# Qwiic_EEPROM.net
KiCad netlist of a schematic drawn in EAGLE
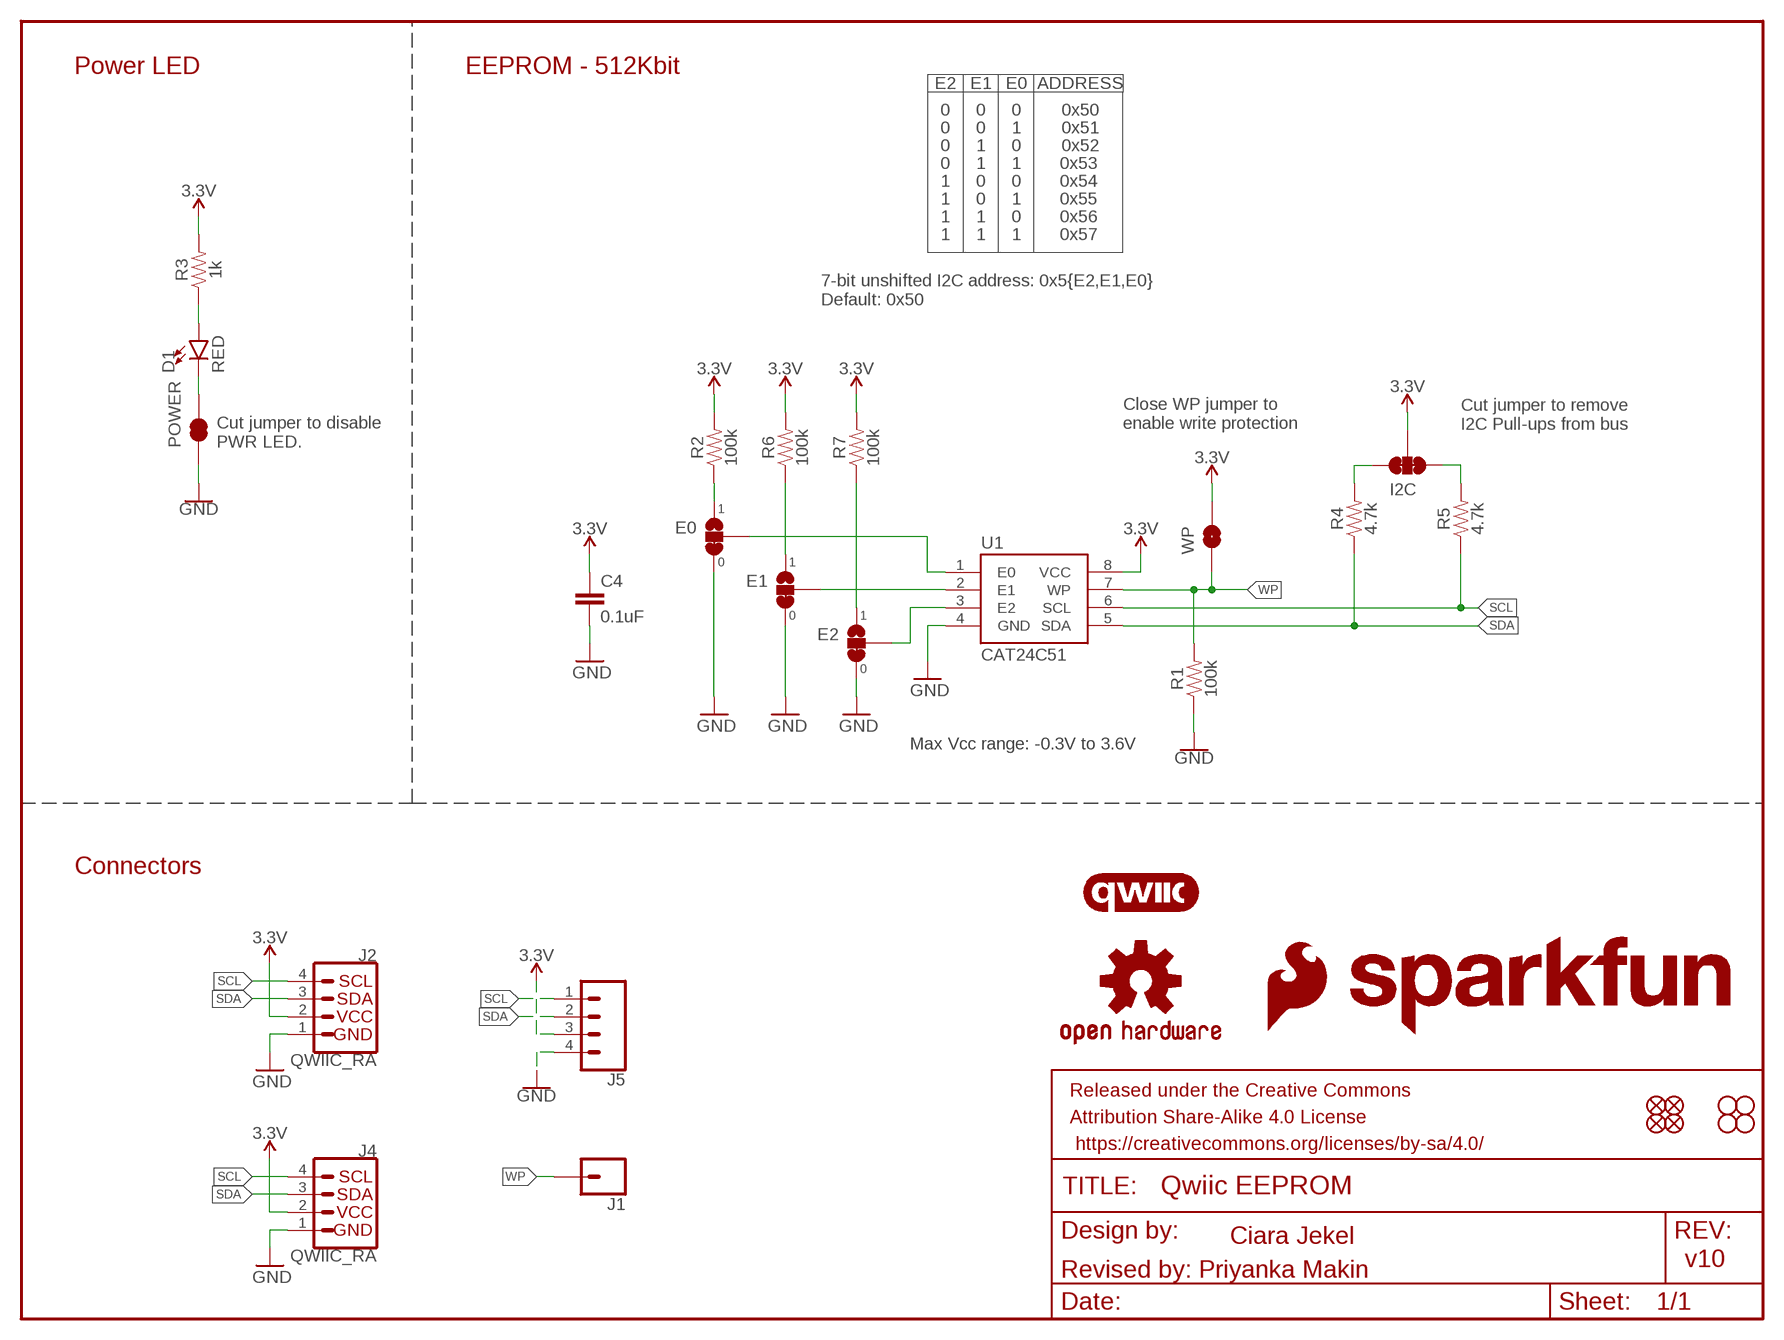
[diagram p0: schematic, sheet 1]

(export (version "E")
  (design (tool "Eeschema 10.0.6"))
  (components
    (comp (ref "C4")
      (value "0.1uF")
      (footprint "eagle-import:0603")
      (libsource (lib "eagle-import") (part "0.1UF-0603-25V-(+80/-20%)"))
    )
    (comp (ref "D1")
      (value "RED")
      (footprint "eagle-import:LED-0603")
      (libsource (lib "eagle-import") (part "LED-RED0603"))
    )
    (comp (ref "E0")
      (value "JUMPER-SMT_3_1-NC_TRACE_SILK")
      (footprint "eagle-import:SMT-JUMPER_3_1-NC_TRACE_SILK")
      (libsource (lib "eagle-import") (part "JUMPER-SMT_3_1-NC_TRACE_SILK"))
    )
    (comp (ref "E1")
      (value "JUMPER-SMT_3_1-NC_TRACE_SILK")
      (footprint "eagle-import:SMT-JUMPER_3_1-NC_TRACE_SILK")
      (libsource (lib "eagle-import") (part "JUMPER-SMT_3_1-NC_TRACE_SILK"))
    )
    (comp (ref "E2")
      (value "JUMPER-SMT_3_1-NC_TRACE_SILK")
      (footprint "eagle-import:SMT-JUMPER_3_1-NC_TRACE_SILK")
      (libsource (lib "eagle-import") (part "JUMPER-SMT_3_1-NC_TRACE_SILK"))
    )
    (comp (ref "FRAME1")
      (value "FRAME-LETTER")
      (footprint "eagle-import:CREATIVE_COMMONS")
      (libsource (lib "eagle-import") (part "FRAME-LETTER"))
    )
    (comp (ref "I2C")
      (value "JUMPER-SMT_3_2-NC_TRACE_SILK")
      (footprint "eagle-import:SMT-JUMPER_3_2-NC_TRACE_SILK")
      (libsource (lib "eagle-import") (part "JUMPER-SMT_3_2-NC_TRACE_SILK"))
    )
    (comp (ref "J1")
      (value "CONN_01PTH_NO_SILK_YES_STOP")
      (footprint "eagle-import:1X01_NO_SILK")
      (libsource (lib "eagle-import") (part "CONN_01PTH_NO_SILK_YES_STOP"))
    )
    (comp (ref "J2")
      (value "QWIIC_RA")
      (footprint "eagle-import:JST04_1MM_RA")
      (libsource (lib "eagle-import") (part "QWIIC_CONNECTORJS-1MM"))
    )
    (comp (ref "J4")
      (value "QWIIC_RA")
      (footprint "eagle-import:JST04_1MM_RA")
      (libsource (lib "eagle-import") (part "QWIIC_CONNECTORJS-1MM"))
    )
    (comp (ref "J5")
      (value "CONN_041X04_NO_SILK_NO_POP")
      (footprint "eagle-import:1X04_NO_SILK")
      (libsource (lib "eagle-import") (part "CONN_041X04_NO_SILK_NO_POP"))
    )
    (comp (ref "JP1")
      (value "FIDUCIALUFIDUCIAL")
      (footprint "eagle-import:FIDUCIAL-MICRO")
      (libsource (lib "eagle-import") (part "FIDUCIALUFIDUCIAL"))
    )
    (comp (ref "JP2")
      (value "FIDUCIALUFIDUCIAL")
      (footprint "eagle-import:FIDUCIAL-MICRO")
      (libsource (lib "eagle-import") (part "FIDUCIALUFIDUCIAL"))
    )
    (comp (ref "JP3")
      (value "STAND-OFF")
      (footprint "eagle-import:STAND-OFF")
      (libsource (lib "eagle-import") (part "STAND-OFF"))
    )
    (comp (ref "JP4")
      (value "STAND-OFF")
      (footprint "eagle-import:STAND-OFF")
      (libsource (lib "eagle-import") (part "STAND-OFF"))
    )
    (comp (ref "JP5")
      (value "FIDUCIALUFIDUCIAL")
      (footprint "eagle-import:FIDUCIAL-MICRO")
      (libsource (lib "eagle-import") (part "FIDUCIALUFIDUCIAL"))
    )
    (comp (ref "JP6")
      (value "FIDUCIALUFIDUCIAL")
      (footprint "eagle-import:FIDUCIAL-MICRO")
      (libsource (lib "eagle-import") (part "FIDUCIALUFIDUCIAL"))
    )
    (comp (ref "JP7")
      (value "STAND-OFF")
      (footprint "eagle-import:STAND-OFF")
      (libsource (lib "eagle-import") (part "STAND-OFF"))
    )
    (comp (ref "JP8")
      (value "STAND-OFF")
      (footprint "eagle-import:STAND-OFF")
      (libsource (lib "eagle-import") (part "STAND-OFF"))
    )
    (comp (ref "LOGO1")
      (value "OSHW-LOGOMINI")
      (footprint "eagle-import:OSHW-LOGO-MINI")
      (libsource (lib "eagle-import") (part "OSHW-LOGOMINI"))
    )
    (comp (ref "LOGO2")
      (value "SFE_LOGO_NAME.1_INCH")
      (footprint "eagle-import:SFE_LOGO_NAME_.1")
      (libsource (lib "eagle-import") (part "SFE_LOGO_NAME.1_INCH"))
    )
    (comp (ref "LOGO3")
      (value "SFE_LOGO_FLAME.1_INCH")
      (footprint "eagle-import:SFE_LOGO_FLAME_.1")
      (libsource (lib "eagle-import") (part "SFE_LOGO_FLAME.1_INCH"))
    )
    (comp (ref "LOGO4")
      (value "QWIIC_LOGO_4MM")
      (footprint "eagle-import:QWIIC_4MM")
      (libsource (lib "eagle-import") (part "QWIIC_LOGO_4MM"))
    )
    (comp (ref "POWER")
      (value "JUMPER-SMT_2_NC_TRACE_SILK")
      (footprint "eagle-import:SMT-JUMPER_2_NC_TRACE_SILK")
      (libsource (lib "eagle-import") (part "JUMPER-SMT_2_NC_TRACE_SILK"))
    )
    (comp (ref "R1")
      (value "100k")
      (footprint "eagle-import:0603")
      (libsource (lib "eagle-import") (part "100KOHM-0603-1/10W-1%"))
    )
    (comp (ref "R2")
      (value "100k")
      (footprint "eagle-import:0603")
      (libsource (lib "eagle-import") (part "100KOHM-0603-1/10W-1%"))
    )
    (comp (ref "R3")
      (value "1k")
      (footprint "eagle-import:0603")
      (libsource (lib "eagle-import") (part "1KOHM-0603-1/10W-1%"))
    )
    (comp (ref "R4")
      (value "4.7k")
      (footprint "eagle-import:0603")
      (libsource (lib "eagle-import") (part "4.7KOHM-0603-1/10W-1%"))
    )
    (comp (ref "R5")
      (value "4.7k")
      (footprint "eagle-import:0603")
      (libsource (lib "eagle-import") (part "4.7KOHM-0603-1/10W-1%"))
    )
    (comp (ref "R6")
      (value "100k")
      (footprint "eagle-import:0603")
      (libsource (lib "eagle-import") (part "100KOHM-0603-1/10W-1%"))
    )
    (comp (ref "R7")
      (value "100k")
      (footprint "eagle-import:0603")
      (libsource (lib "eagle-import") (part "100KOHM-0603-1/10W-1%"))
    )
    (comp (ref "U1")
      (value "CAT24C51")
      (footprint "eagle-import:SO08")
      (libsource (lib "eagle-import") (part "RM24C512C"))
    )
    (comp (ref "WP")
      (value "JUMPER-SMT_2_NO_SILK")
      (footprint "eagle-import:SMT-JUMPER_2_NO_SILK")
      (libsource (lib "eagle-import") (part "JUMPER-SMT_2_NO_SILK"))
    )
  )
  (nets
    (net (code "1") (name "3.3V") (class "Default")
      (node (ref "C4") (pin "1") (pinfunction "1_1") (pintype "passive"))
      (node (ref "I2C") (pin "2") (pinfunction "2_2") (pintype "passive"))
      (node (ref "J2") (pin "2") (pinfunction "2_2") (pintype "power_in"))
      (node (ref "J4") (pin "2") (pinfunction "2_2") (pintype "power_in"))
      (node (ref "J5") (pin "3") (pinfunction "3_3") (pintype "passive"))
      (node (ref "R2") (pin "2") (pinfunction "2_2") (pintype "passive"))
      (node (ref "R3") (pin "2") (pinfunction "2_2") (pintype "passive"))
      (node (ref "R6") (pin "2") (pinfunction "2_2") (pintype "passive"))
      (node (ref "R7") (pin "2") (pinfunction "2_2") (pintype "passive"))
      (node (ref "U1") (pin "8") (pinfunction "VCC_8") (pintype "power_in"))
      (node (ref "WP") (pin "2") (pinfunction "2_2") (pintype "passive"))
    )
    (net (code "2") (name "GND") (class "Default")
      (node (ref "C4") (pin "2") (pinfunction "2_2") (pintype "passive"))
      (node (ref "E0") (pin "3") (pinfunction "3_3") (pintype "passive"))
      (node (ref "E1") (pin "3") (pinfunction "3_3") (pintype "passive"))
      (node (ref "E2") (pin "3") (pinfunction "3_3") (pintype "passive"))
      (node (ref "J2") (pin "1") (pinfunction "1_1") (pintype "power_in"))
      (node (ref "J4") (pin "1") (pinfunction "1_1") (pintype "power_in"))
      (node (ref "J5") (pin "4") (pinfunction "4_4") (pintype "passive"))
      (node (ref "POWER") (pin "1") (pinfunction "1_1") (pintype "passive"))
      (node (ref "R1") (pin "1") (pinfunction "1_1") (pintype "passive"))
      (node (ref "U1") (pin "4") (pinfunction "GND_4") (pintype "power_in"))
    )
    (net (code "3") (name "Net-(D1-PadA)") (class "Default")
      (node (ref "D1") (pin "A") (pinfunction "A_A") (pintype "passive"))
      (node (ref "R3") (pin "1") (pinfunction "1_1") (pintype "passive"))
    )
    (net (code "4") (name "Net-(D1-PadC)") (class "Default")
      (node (ref "D1") (pin "C") (pinfunction "C_C") (pintype "passive"))
      (node (ref "POWER") (pin "2") (pinfunction "2_2") (pintype "passive"))
    )
    (net (code "5") (name "Net-(E0-Pad1)") (class "Default")
      (node (ref "E0") (pin "1") (pinfunction "1_1") (pintype "passive"))
      (node (ref "R2") (pin "1") (pinfunction "1_1") (pintype "passive"))
    )
    (net (code "6") (name "Net-(E1-Pad1)") (class "Default")
      (node (ref "E1") (pin "1") (pinfunction "1_1") (pintype "passive"))
      (node (ref "R6") (pin "1") (pinfunction "1_1") (pintype "passive"))
    )
    (net (code "7") (name "Net-(E2-Pad1)") (class "Default")
      (node (ref "E2") (pin "1") (pinfunction "1_1") (pintype "passive"))
      (node (ref "R7") (pin "1") (pinfunction "1_1") (pintype "passive"))
    )
    (net (code "8") (name "Net-(I2C-Pad1)") (class "Default")
      (node (ref "I2C") (pin "1") (pinfunction "1_1") (pintype "passive"))
      (node (ref "R5") (pin "2") (pinfunction "2_2") (pintype "passive"))
    )
    (net (code "9") (name "Net-(I2C-Pad3)") (class "Default")
      (node (ref "I2C") (pin "3") (pinfunction "3_3") (pintype "passive"))
      (node (ref "R4") (pin "2") (pinfunction "2_2") (pintype "passive"))
    )
    (net (code "10") (name "Net-(U1-E0)") (class "Default")
      (node (ref "E0") (pin "2") (pinfunction "2_2") (pintype "passive"))
      (node (ref "U1") (pin "1") (pinfunction "E0_1") (pintype "bidirectional"))
    )
    (net (code "11") (name "Net-(U1-E1)") (class "Default")
      (node (ref "E1") (pin "2") (pinfunction "2_2") (pintype "passive"))
      (node (ref "U1") (pin "2") (pinfunction "E1_2") (pintype "bidirectional"))
    )
    (net (code "12") (name "Net-(U1-E2)") (class "Default")
      (node (ref "E2") (pin "2") (pinfunction "2_2") (pintype "passive"))
      (node (ref "U1") (pin "3") (pinfunction "E2_3") (pintype "bidirectional"))
    )
    (net (code "13") (name "SCL") (class "Default")
      (node (ref "J2") (pin "4") (pinfunction "4_4") (pintype "passive"))
      (node (ref "J4") (pin "4") (pinfunction "4_4") (pintype "passive"))
      (node (ref "J5") (pin "1") (pinfunction "1_1") (pintype "passive"))
      (node (ref "R5") (pin "1") (pinfunction "1_1") (pintype "passive"))
      (node (ref "U1") (pin "6") (pinfunction "SCL_6") (pintype "bidirectional"))
    )
    (net (code "14") (name "SDA") (class "Default")
      (node (ref "J2") (pin "3") (pinfunction "3_3") (pintype "passive"))
      (node (ref "J4") (pin "3") (pinfunction "3_3") (pintype "passive"))
      (node (ref "J5") (pin "2") (pinfunction "2_2") (pintype "passive"))
      (node (ref "R4") (pin "1") (pinfunction "1_1") (pintype "passive"))
      (node (ref "U1") (pin "5") (pinfunction "SDA_5") (pintype "bidirectional"))
    )
    (net (code "15") (name "WP") (class "Default")
      (node (ref "J1") (pin "1") (pinfunction "1_1") (pintype "passive"))
      (node (ref "R1") (pin "2") (pinfunction "2_2") (pintype "passive"))
      (node (ref "U1") (pin "7") (pinfunction "WP_7") (pintype "bidirectional"))
      (node (ref "WP") (pin "1") (pinfunction "1_1") (pintype "passive"))
    )
  )
)
